# Headers.net
KiCad netlist of a schematic drawn in Altium Designer
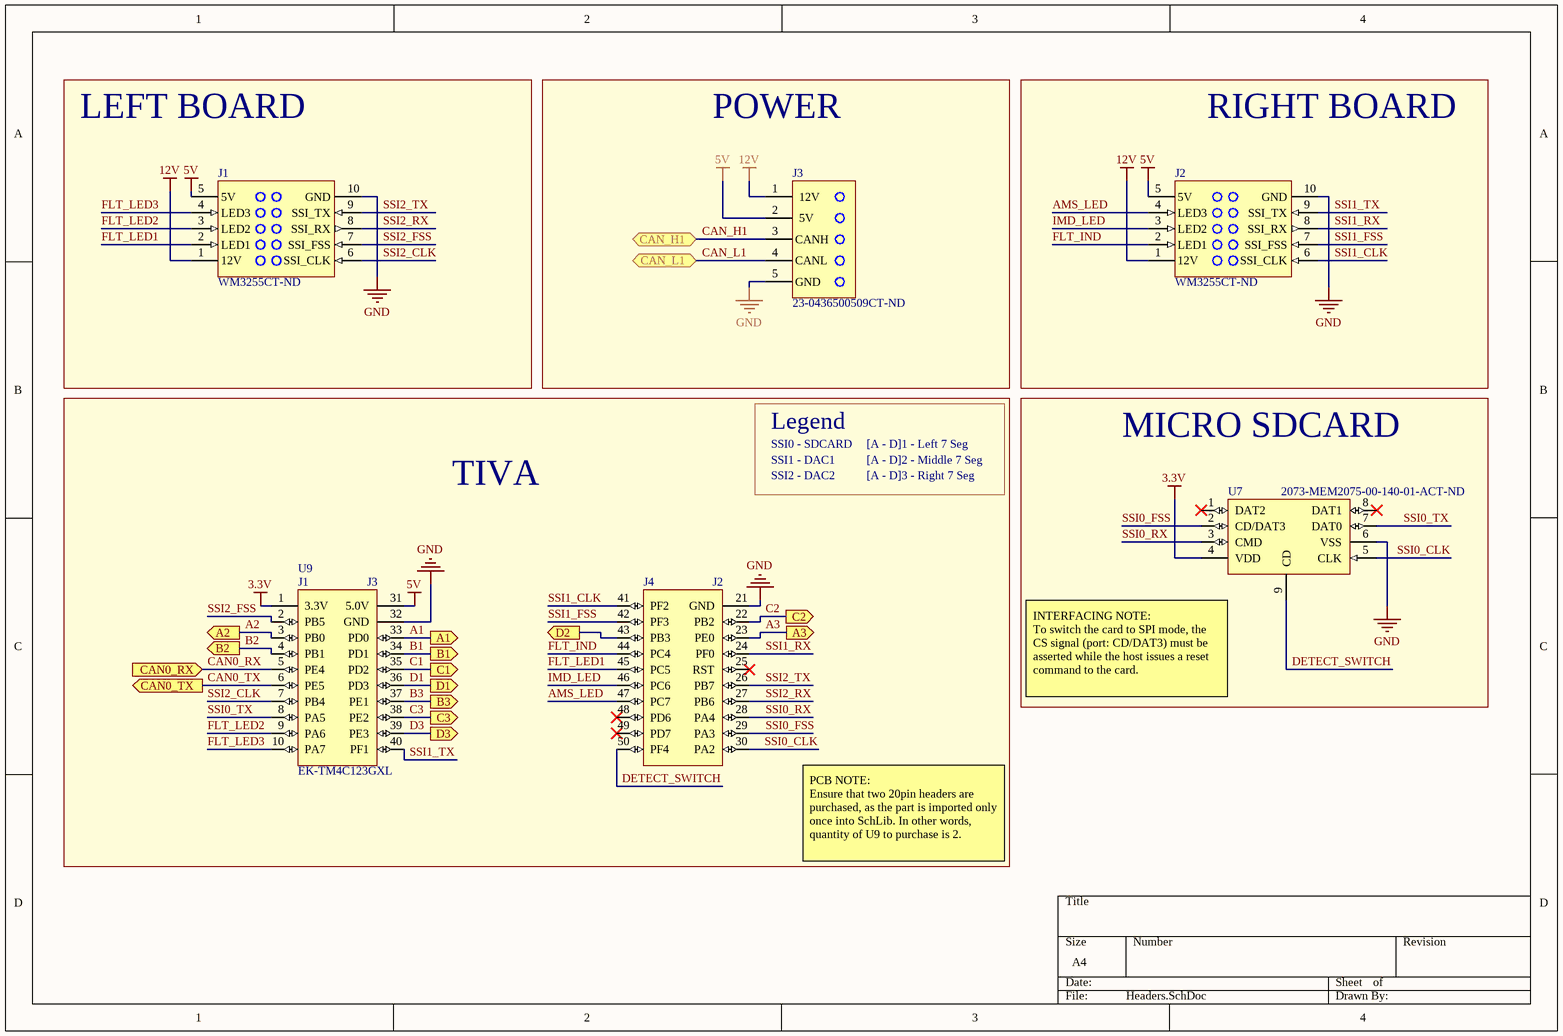
[diagram p0: Headers.SchDoc]

(export (version "E")
  (design (tool "Eeschema 10.0.6"))
  (components
    (comp (ref "J1")
      (value "WM3255CT-ND")
      (footprint "MOLEX-10PIN")
      (description "HEADER R/A 10POS DUAL TIN SMD")
      (fields (field (name "MANUFACTURER") "Molex") (field (name "MANUFACTURER PART NUMBER") "0430451006"))
      (libsource (lib "Dashboard") (part "MOLEX-10PIN"))
    )
    (comp (ref "J2")
      (value "WM3255CT-ND")
      (footprint "MOLEX-10PIN")
      (description "HEADER R/A 10POS DUAL TIN SMD")
      (fields (field (name "MANUFACTURER") "Molex") (field (name "MANUFACTURER PART NUMBER") "0430451006"))
      (libsource (lib "Dashboard") (part "MOLEX-10PIN"))
    )
    (comp (ref "J3")
      (value "23-0436500509CT-ND")
      (footprint "MOLEX-5PIN")
      (description "GLOVE, POLYAMIDE, L/FREE, PU, SIZE 6 - More Details")
      (fields (field (name "MANUFACTURER") "Molex") (field (name "MANUFACTURER PART NUMBER") "0436500509"))
      (libsource (lib "Dashboard") (part "0436500509"))
    )
    (comp (ref "U7")
      (value "2073-MEM2075-00-140-01-ACT-ND")
      (footprint "SDCARD-NORMAL")
      (description "850NM POINT SOURCE LED ASSY")
      (fields
        (field (name "MANUFACTURER") "Global Connector Technology")
        (field (name "MANUFACTURER PART NUMBER") "MEM2075-00-140-01-A")
      )
      (libsource (lib "Dashboard") (part "SDCARD CONN."))
    )
    (comp (ref "U9")
      (value "EK-TM4C123GXL")
      (footprint "TIVA Headers")
      (description "PH Series 20 Position Through-Hole Dual Row Straight .100 Header")
      (fields
        (field (name "MANUFACTURER") "Adam Equipment")
        (field (name "MANUFACTURER PART NUMBER") "PH2-20-UA")
      )
      (libsource (lib "Dashboard") (part "PH2-20-UA"))
    )
  )
  (nets
    (net (code "1") (name "/A1") (class "Default")
      (node (ref "U9") (pin "33") (pinfunction "PD0_33") (pintype "bidirectional"))
    )
    (net (code "2") (name "/A2") (class "Default")
      (node (ref "U9") (pin "3") (pinfunction "PB0_3") (pintype "bidirectional"))
    )
    (net (code "3") (name "/A3") (class "Default")
      (node (ref "U9") (pin "23") (pinfunction "PE0_23") (pintype "bidirectional"))
    )
    (net (code "4") (name "/AMS_LED") (class "Default")
      (node (ref "J2") (pin "4") (pinfunction "LED3_4") (pintype "input"))
      (node (ref "U9") (pin "47") (pinfunction "PC7_47") (pintype "bidirectional"))
    )
    (net (code "5") (name "/B1") (class "Default")
      (node (ref "U9") (pin "34") (pinfunction "PD1_34") (pintype "bidirectional"))
    )
    (net (code "6") (name "/B2") (class "Default")
      (node (ref "U9") (pin "4") (pinfunction "PB1_4") (pintype "bidirectional"))
    )
    (net (code "7") (name "/B3") (class "Default")
      (node (ref "U9") (pin "37") (pinfunction "PE1_37") (pintype "bidirectional"))
    )
    (net (code "8") (name "/C1") (class "Default")
      (node (ref "U9") (pin "35") (pinfunction "PD2_35") (pintype "bidirectional"))
    )
    (net (code "9") (name "/C2") (class "Default")
      (node (ref "U9") (pin "22") (pinfunction "PB2_22") (pintype "bidirectional"))
    )
    (net (code "10") (name "/C3") (class "Default")
      (node (ref "U9") (pin "38") (pinfunction "PE2_38") (pintype "bidirectional"))
    )
    (net (code "11") (name "/CAN0_RX") (class "Default")
      (node (ref "U9") (pin "5") (pinfunction "PE4_5") (pintype "bidirectional"))
    )
    (net (code "12") (name "/CAN0_TX") (class "Default")
      (node (ref "U9") (pin "6") (pinfunction "PE5_6") (pintype "bidirectional"))
    )
    (net (code "13") (name "/CAN_H1") (class "Default")
      (node (ref "J3") (pin "3") (pinfunction "CANH_3") (pintype "passive"))
    )
    (net (code "14") (name "/CAN_L1") (class "Default")
      (node (ref "J3") (pin "4") (pinfunction "CANL_4") (pintype "passive"))
    )
    (net (code "15") (name "/D1") (class "Default")
      (node (ref "U9") (pin "36") (pinfunction "PD3_36") (pintype "bidirectional"))
    )
    (net (code "16") (name "/D2") (class "Default")
      (node (ref "U9") (pin "43") (pinfunction "PB3_43") (pintype "bidirectional"))
    )
    (net (code "17") (name "/D3") (class "Default")
      (node (ref "U9") (pin "39") (pinfunction "PE3_39") (pintype "bidirectional"))
    )
    (net (code "18") (name "/DETECT_SWITCH") (class "Default")
      (node (ref "U7") (pin "9") (pinfunction "CD_9") (pintype "passive"))
      (node (ref "U9") (pin "50") (pinfunction "PF4_50") (pintype "bidirectional"))
    )
    (net (code "19") (name "/FLT_IND") (class "Default")
      (node (ref "J2") (pin "2") (pinfunction "LED1_2") (pintype "input"))
      (node (ref "U9") (pin "44") (pinfunction "PC4_44") (pintype "bidirectional"))
    )
    (net (code "20") (name "/FLT_LED1") (class "Default")
      (node (ref "J1") (pin "2") (pinfunction "LED1_2") (pintype "input"))
      (node (ref "U9") (pin "45") (pinfunction "PC5_45") (pintype "bidirectional"))
    )
    (net (code "21") (name "/FLT_LED2") (class "Default")
      (node (ref "J1") (pin "3") (pinfunction "LED2_3") (pintype "input"))
      (node (ref "U9") (pin "9") (pinfunction "PA6_9") (pintype "bidirectional"))
    )
    (net (code "22") (name "/FLT_LED3") (class "Default")
      (node (ref "J1") (pin "4") (pinfunction "LED3_4") (pintype "input"))
      (node (ref "U9") (pin "10") (pinfunction "PA7_10") (pintype "bidirectional"))
    )
    (net (code "23") (name "/IMD_LED") (class "Default")
      (node (ref "J2") (pin "3") (pinfunction "LED2_3") (pintype "input"))
      (node (ref "U9") (pin "46") (pinfunction "PC6_46") (pintype "bidirectional"))
    )
    (net (code "24") (name "/SSI0_CLK") (class "Default")
      (node (ref "U7") (pin "5") (pinfunction "CLK_5") (pintype "input"))
      (node (ref "U9") (pin "30") (pinfunction "PA2_30") (pintype "bidirectional"))
    )
    (net (code "25") (name "/SSI0_FSS") (class "Default")
      (node (ref "U7") (pin "2") (pinfunction "CD/DAT3_2") (pintype "bidirectional"))
      (node (ref "U9") (pin "29") (pinfunction "PA3_29") (pintype "bidirectional"))
    )
    (net (code "26") (name "/SSI0_RX") (class "Default")
      (node (ref "U7") (pin "3") (pinfunction "CMD_3") (pintype "bidirectional"))
      (node (ref "U9") (pin "28") (pinfunction "PA4_28") (pintype "bidirectional"))
    )
    (net (code "27") (name "/SSI0_TX") (class "Default")
      (node (ref "U7") (pin "7") (pinfunction "DAT0_7") (pintype "bidirectional"))
      (node (ref "U9") (pin "8") (pinfunction "PA5_8") (pintype "bidirectional"))
    )
    (net (code "28") (name "/SSI1_CLK") (class "Default")
      (node (ref "J2") (pin "6") (pinfunction "SSI_CLK_6") (pintype "input"))
      (node (ref "U9") (pin "41") (pinfunction "PF2_41") (pintype "bidirectional"))
    )
    (net (code "29") (name "/SSI1_FSS") (class "Default")
      (node (ref "J2") (pin "7") (pinfunction "SSI_FSS_7") (pintype "input"))
      (node (ref "U9") (pin "42") (pinfunction "PF3_42") (pintype "bidirectional"))
    )
    (net (code "30") (name "/SSI1_RX") (class "Default")
      (node (ref "J2") (pin "8") (pinfunction "SSI_RX_8") (pintype "output"))
      (node (ref "U9") (pin "24") (pinfunction "PF0_24") (pintype "bidirectional"))
    )
    (net (code "31") (name "/SSI1_TX") (class "Default")
      (node (ref "J2") (pin "9") (pinfunction "SSI_TX_9") (pintype "input"))
      (node (ref "U9") (pin "40") (pinfunction "PF1_40") (pintype "bidirectional"))
    )
    (net (code "32") (name "/SSI2_CLK") (class "Default")
      (node (ref "J1") (pin "6") (pinfunction "SSI_CLK_6") (pintype "input"))
      (node (ref "U9") (pin "7") (pinfunction "PB4_7") (pintype "bidirectional"))
    )
    (net (code "33") (name "/SSI2_FSS") (class "Default")
      (node (ref "J1") (pin "7") (pinfunction "SSI_FSS_7") (pintype "input"))
      (node (ref "U9") (pin "2") (pinfunction "PB5_2") (pintype "bidirectional"))
    )
    (net (code "34") (name "/SSI2_RX") (class "Default")
      (node (ref "J1") (pin "8") (pinfunction "SSI_RX_8") (pintype "output"))
      (node (ref "U9") (pin "27") (pinfunction "PB6_27") (pintype "bidirectional"))
    )
    (net (code "35") (name "/SSI2_TX") (class "Default")
      (node (ref "J1") (pin "9") (pinfunction "SSI_TX_9") (pintype "input"))
      (node (ref "U9") (pin "26") (pinfunction "PB7_26") (pintype "bidirectional"))
    )
    (net (code "36") (name "3.3V") (class "Default")
      (node (ref "U7") (pin "4") (pinfunction "VDD_4") (pintype "power_in"))
      (node (ref "U9") (pin "1") (pinfunction "3.3V_1") (pintype "power_in"))
    )
    (net (code "37") (name "5V") (class "Default")
      (node (ref "J1") (pin "5") (pinfunction "5V_5") (pintype "power_in"))
      (node (ref "J2") (pin "5") (pinfunction "5V_5") (pintype "power_in"))
      (node (ref "J3") (pin "2") (pinfunction "5V_2") (pintype "power_in"))
      (node (ref "U9") (pin "31") (pinfunction "5.0V_31") (pintype "power_in"))
    )
    (net (code "38") (name "12V") (class "Default")
      (node (ref "J1") (pin "1") (pinfunction "12V_1") (pintype "power_in"))
      (node (ref "J2") (pin "1") (pinfunction "12V_1") (pintype "power_in"))
      (node (ref "J3") (pin "1") (pinfunction "12V_1") (pintype "power_in"))
    )
    (net (code "39") (name "GND") (class "Default")
      (node (ref "J1") (pin "10") (pinfunction "GND_10") (pintype "power_in"))
      (node (ref "J2") (pin "10") (pinfunction "GND_10") (pintype "power_in"))
      (node (ref "J3") (pin "5") (pinfunction "GND_5") (pintype "power_in"))
      (node (ref "U7") (pin "6") (pinfunction "VSS_6") (pintype "power_in"))
      (node (ref "U9") (pin "21") (pinfunction "GND_21") (pintype "power_in"))
      (node (ref "U9") (pin "32") (pinfunction "GND_32") (pintype "power_in"))
    )
    (net (code "40") (name "unconnected-(U7-DAT1-Pad8)") (class "Default")
      (node (ref "U7") (pin "8") (pinfunction "DAT1_8") (pintype "bidirectional+no_connect"))
    )
    (net (code "41") (name "unconnected-(U7-DAT2-Pad1)") (class "Default")
      (node (ref "U7") (pin "1") (pinfunction "DAT2_1") (pintype "bidirectional+no_connect"))
    )
    (net (code "42") (name "unconnected-(U9-PD6-Pad48)") (class "Default")
      (node (ref "U9") (pin "48") (pinfunction "PD6_48") (pintype "bidirectional+no_connect"))
    )
    (net (code "43") (name "unconnected-(U9-PD7-Pad49)") (class "Default")
      (node (ref "U9") (pin "49") (pinfunction "PD7_49") (pintype "bidirectional+no_connect"))
    )
    (net (code "44") (name "unconnected-(U9-RST-Pad25)") (class "Default")
      (node (ref "U9") (pin "25") (pinfunction "RST_25") (pintype "bidirectional+no_connect"))
    )
  )
)
